# ece411_t2_schematic_5.net
KiCad netlist of a schematic drawn in EAGLE
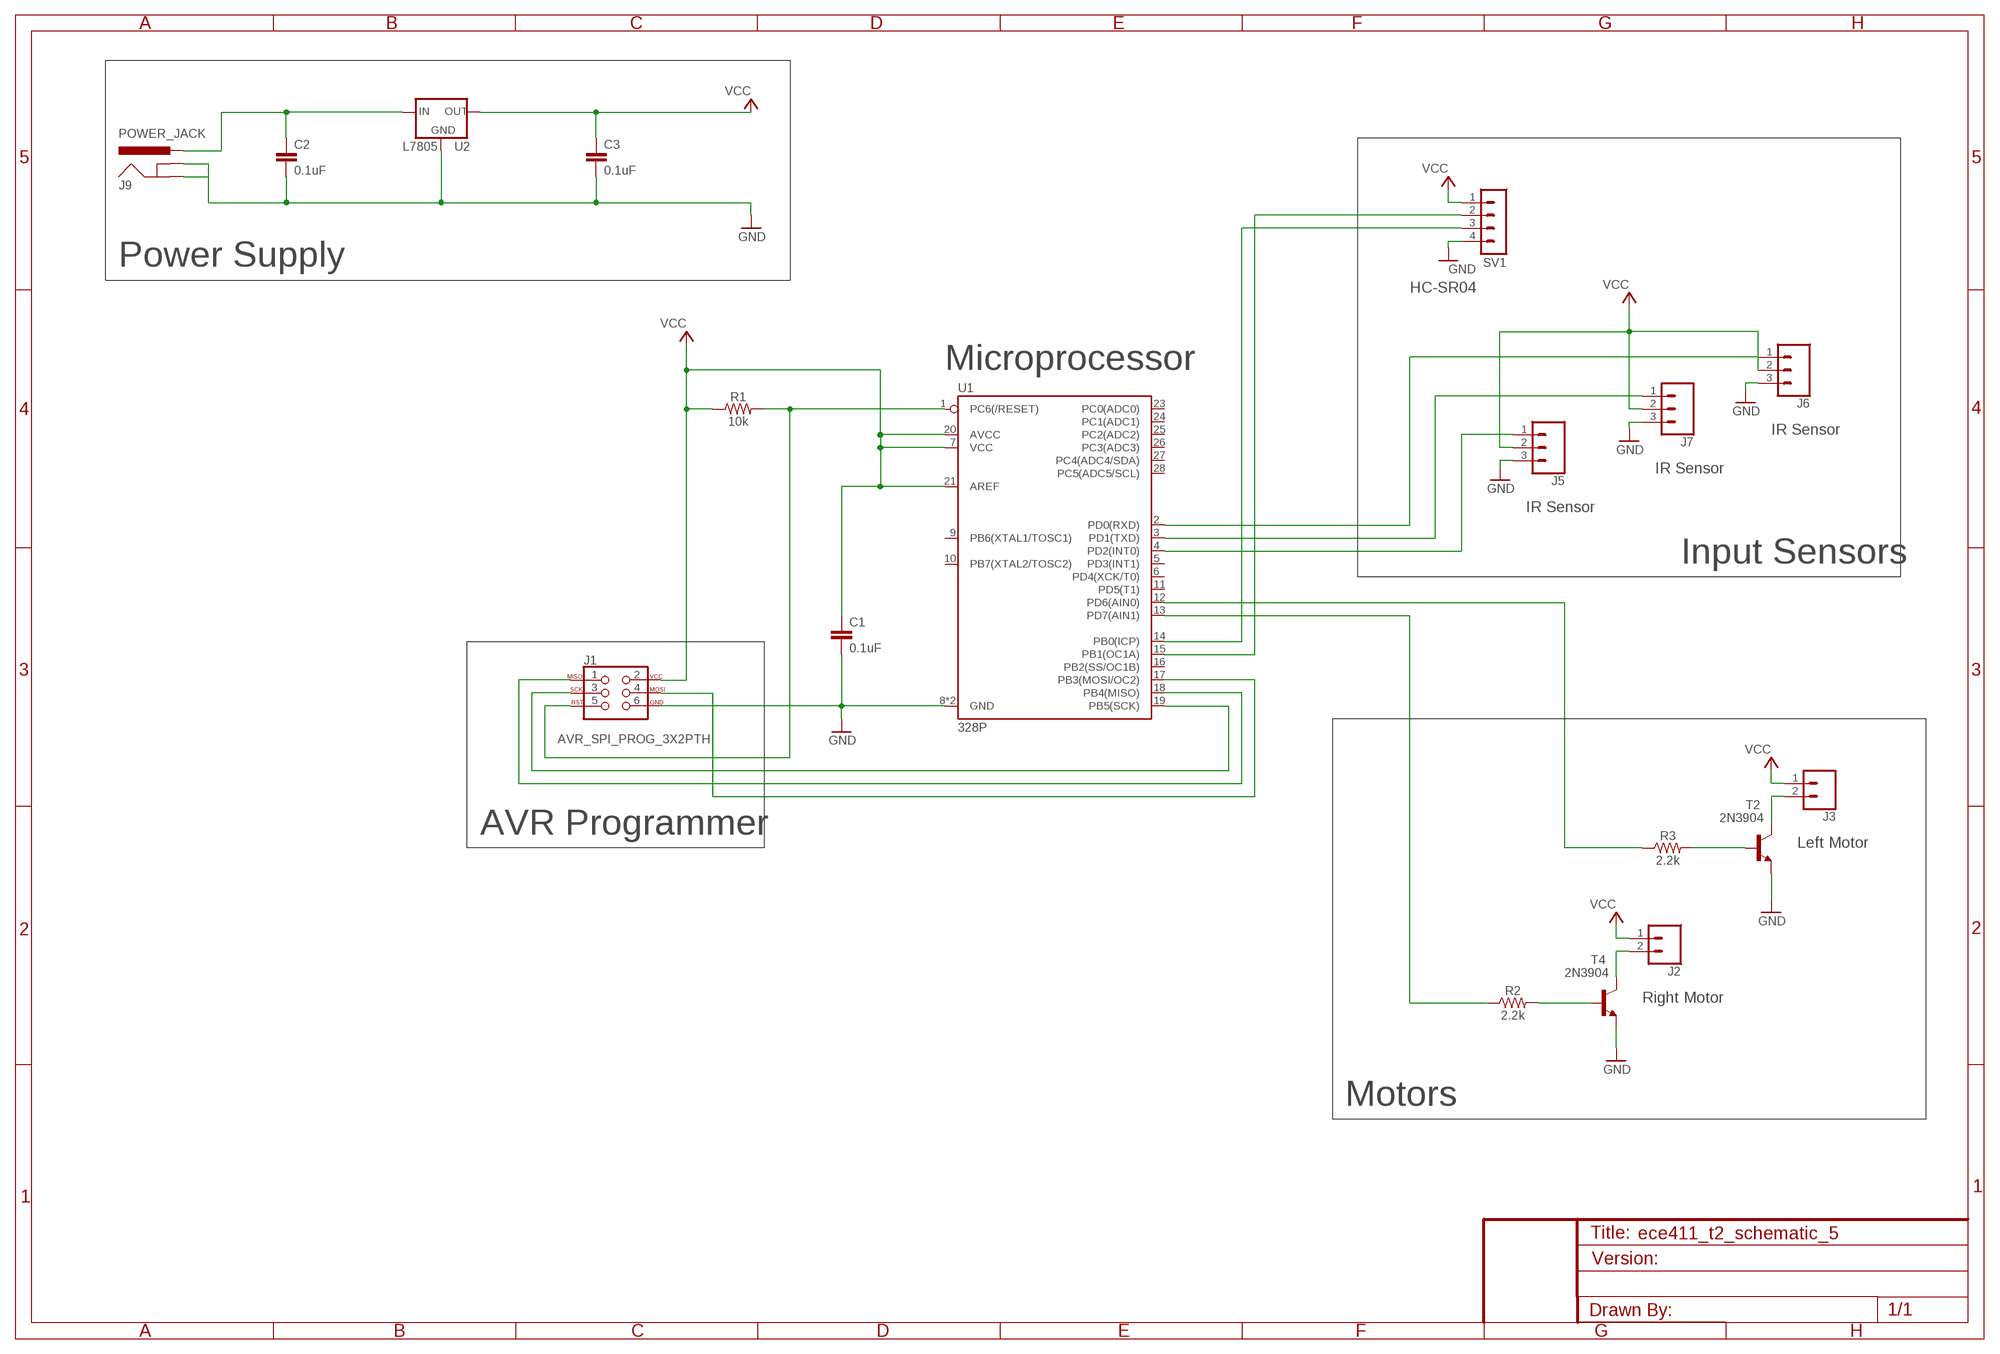
[diagram p0: schematic, sheet 1]

(export (version "E")
  (design (tool "Eeschema 10.0.6"))
  (components
    (comp (ref "C1")
      (value "0.1uF")
      (footprint "eagle-import:0402")
      (libsource (lib "eagle-import") (part "0.1UF-0402-6.3V-10%-X7R"))
    )
    (comp (ref "C2")
      (value "0.1uF")
      (footprint "eagle-import:0402")
      (libsource (lib "eagle-import") (part "0.1UF-0402-6.3V-10%-X7R"))
    )
    (comp (ref "C3")
      (value "0.1uF")
      (footprint "eagle-import:0402")
      (libsource (lib "eagle-import") (part "0.1UF-0402-6.3V-10%-X7R"))
    )
    (comp (ref "J1")
      (value "AVR_SPI_PROG_3X2PTH")
      (footprint "eagle-import:2X3")
      (libsource (lib "eagle-import") (part "AVR_SPI_PROG_3X2PTH"))
    )
    (comp (ref "J2")
      (value "CONN_02")
      (footprint "eagle-import:1X02")
      (libsource (lib "eagle-import") (part "CONN_02"))
    )
    (comp (ref "J3")
      (value "CONN_02")
      (footprint "eagle-import:1X02")
      (libsource (lib "eagle-import") (part "CONN_02"))
    )
    (comp (ref "J5")
      (value "455-1750-1-ND")
      (footprint "eagle-import:1X03")
      (libsource (lib "eagle-import") (part "CONN_03"))
    )
    (comp (ref "J6")
      (value "455-1750-1-ND")
      (footprint "eagle-import:1X03")
      (libsource (lib "eagle-import") (part "CONN_03"))
    )
    (comp (ref "J7")
      (value "455-1750-1-ND")
      (footprint "eagle-import:1X03")
      (libsource (lib "eagle-import") (part "CONN_03"))
    )
    (comp (ref "J9")
      (value "POWER_JACK")
      (footprint "eagle-import:POWER_JACK_PTH")
      (libsource (lib "eagle-import") (part "POWER_JACK"))
    )
    (comp (ref "R1")
      (value "10k")
      (footprint "eagle-import:0402")
      (libsource (lib "eagle-import") (part "10KOHM-0402-1/16W-1%"))
    )
    (comp (ref "R2")
      (value "2.2k")
      (footprint "eagle-import:0603")
      (libsource (lib "eagle-import") (part "2.2KOHM-0603-1/10W-1%"))
    )
    (comp (ref "R3")
      (value "2.2k")
      (footprint "eagle-import:0603")
      (libsource (lib "eagle-import") (part "2.2KOHM-0603-1/10W-1%"))
    )
    (comp (ref "SV1")
      (value "MA04-1")
      (footprint "eagle-import:MA04-1")
      (libsource (lib "eagle-import") (part "MA04-1"))
    )
    (comp (ref "T2")
      (value "2N3904")
      (footprint "eagle-import:TO92")
      (libsource (lib "eagle-import") (part "2N3904"))
    )
    (comp (ref "T4")
      (value "2N3904")
      (footprint "eagle-import:TO92")
      (libsource (lib "eagle-import") (part "2N3904"))
    )
    (comp (ref "U1")
      (value "328P")
      (footprint "eagle-import:DIP28")
      (libsource (lib "eagle-import") (part "ATMEGA328P_PDIP"))
    )
    (comp (ref "U2")
      (value "V_REG_78XX-TO-220")
      (footprint "eagle-import:TO-220-ALT")
      (libsource (lib "eagle-import") (part "V_REG_78XX-TO-220"))
    )
  )
  (nets
    (net (code "1") (name "GND") (class "Default")
      (node (ref "C1") (pin "2") (pinfunction "2_2") (pintype "passive"))
      (node (ref "C2") (pin "2") (pinfunction "2_2") (pintype "passive"))
      (node (ref "C3") (pin "2") (pinfunction "2_2") (pintype "passive"))
      (node (ref "J1") (pin "6") (pinfunction "6_6") (pintype "passive"))
      (node (ref "J5") (pin "3") (pinfunction "3_3") (pintype "passive"))
      (node (ref "J6") (pin "3") (pinfunction "3_3") (pintype "passive"))
      (node (ref "J7") (pin "3") (pinfunction "3_3") (pintype "passive"))
      (node (ref "J9") (pin "GNDBREAK") (pinfunction "GNDBREAK_GNDBREAK") (pintype "bidirectional"))
      (node (ref "SV1") (pin "4") (pinfunction "4_4") (pintype "passive"))
      (node (ref "T2") (pin "3") (pinfunction "E_3") (pintype "passive"))
      (node (ref "T4") (pin "3") (pinfunction "E_3") (pintype "passive"))
      (node (ref "U1") (pin "22") (pinfunction "GND_22") (pintype "bidirectional"))
      (node (ref "U1") (pin "8") (pinfunction "GND_8") (pintype "bidirectional"))
      (node (ref "U2") (pin "GND") (pinfunction "GND_GND") (pintype "input"))
    )
    (net (code "2") (name "Net-(C2-Pad1)") (class "Default")
      (node (ref "C2") (pin "1") (pinfunction "1_1") (pintype "passive"))
      (node (ref "J9") (pin "PWR") (pinfunction "PWR_PWR") (pintype "bidirectional"))
      (node (ref "U2") (pin "IN") (pinfunction "IN_IN") (pintype "input"))
    )
    (net (code "3") (name "Net-(T2-B)") (class "Default")
      (node (ref "R3") (pin "2") (pinfunction "2_2") (pintype "passive"))
      (node (ref "T2") (pin "2") (pinfunction "B_2") (pintype "passive"))
    )
    (net (code "4") (name "Net-(T2-C)") (class "Default")
      (node (ref "J3") (pin "2") (pinfunction "2_2") (pintype "passive"))
      (node (ref "T2") (pin "1") (pinfunction "C_1") (pintype "passive"))
    )
    (net (code "5") (name "Net-(T4-B)") (class "Default")
      (node (ref "R2") (pin "2") (pinfunction "2_2") (pintype "passive"))
      (node (ref "T4") (pin "2") (pinfunction "B_2") (pintype "passive"))
    )
    (net (code "6") (name "Net-(U1-PB0(ICP))") (class "Default")
      (node (ref "SV1") (pin "3") (pinfunction "3_3") (pintype "passive"))
      (node (ref "U1") (pin "14") (pinfunction "PB0(ICP)_14") (pintype "bidirectional"))
    )
    (net (code "7") (name "Net-(U1-PB1(OC1A))") (class "Default")
      (node (ref "SV1") (pin "2") (pinfunction "2_2") (pintype "passive"))
      (node (ref "U1") (pin "15") (pinfunction "PB1(OC1A)_15") (pintype "bidirectional"))
    )
    (net (code "8") (name "Net-(U1-PB3(MOSI{slash}OC2))") (class "Default")
      (node (ref "J1") (pin "4") (pinfunction "4_4") (pintype "passive"))
      (node (ref "U1") (pin "17") (pinfunction "PB3(MOSI/OC2)_17") (pintype "bidirectional"))
    )
    (net (code "9") (name "Net-(U1-PB4(MISO))") (class "Default")
      (node (ref "J1") (pin "1") (pinfunction "1_1") (pintype "passive"))
      (node (ref "U1") (pin "18") (pinfunction "PB4(MISO)_18") (pintype "bidirectional"))
    )
    (net (code "10") (name "Net-(U1-PB5(SCK))") (class "Default")
      (node (ref "J1") (pin "3") (pinfunction "3_3") (pintype "passive"))
      (node (ref "U1") (pin "19") (pinfunction "PB5(SCK)_19") (pintype "bidirectional"))
    )
    (net (code "11") (name "Net-(U1-PC6({slash}RESET))") (class "Default")
      (node (ref "J1") (pin "5") (pinfunction "5_5") (pintype "passive"))
      (node (ref "R1") (pin "2") (pinfunction "2_2") (pintype "passive"))
      (node (ref "U1") (pin "1") (pinfunction "PC6(/RESET)_1") (pintype "bidirectional"))
    )
    (net (code "12") (name "Net-(U1-PD0(RXD))") (class "Default")
      (node (ref "J6") (pin "1") (pinfunction "1_1") (pintype "passive"))
      (node (ref "U1") (pin "2") (pinfunction "PD0(RXD)_2") (pintype "bidirectional"))
    )
    (net (code "13") (name "Net-(U1-PD1(TXD))") (class "Default")
      (node (ref "J7") (pin "1") (pinfunction "1_1") (pintype "passive"))
      (node (ref "U1") (pin "3") (pinfunction "PD1(TXD)_3") (pintype "bidirectional"))
    )
    (net (code "14") (name "Net-(U1-PD2(INT0))") (class "Default")
      (node (ref "J5") (pin "1") (pinfunction "1_1") (pintype "passive"))
      (node (ref "U1") (pin "4") (pinfunction "PD2(INT0)_4") (pintype "bidirectional"))
    )
    (net (code "15") (name "Net-(U1-PD6(AIN0))") (class "Default")
      (node (ref "R3") (pin "1") (pinfunction "1_1") (pintype "passive"))
      (node (ref "U1") (pin "12") (pinfunction "PD6(AIN0)_12") (pintype "bidirectional"))
    )
    (net (code "16") (name "Net-(U1-PD7(AIN1))") (class "Default")
      (node (ref "R2") (pin "1") (pinfunction "1_1") (pintype "passive"))
      (node (ref "U1") (pin "13") (pinfunction "PD7(AIN1)_13") (pintype "bidirectional"))
    )
    (net (code "17") (name "VCC") (class "Default")
      (node (ref "C1") (pin "1") (pinfunction "1_1") (pintype "passive"))
      (node (ref "C3") (pin "1") (pinfunction "1_1") (pintype "passive"))
      (node (ref "J1") (pin "2") (pinfunction "2_2") (pintype "passive"))
      (node (ref "J2") (pin "1") (pinfunction "1_1") (pintype "passive"))
      (node (ref "J2") (pin "2") (pinfunction "2_2") (pintype "passive"))
      (node (ref "J3") (pin "1") (pinfunction "1_1") (pintype "passive"))
      (node (ref "J5") (pin "2") (pinfunction "2_2") (pintype "passive"))
      (node (ref "J6") (pin "2") (pinfunction "2_2") (pintype "passive"))
      (node (ref "J7") (pin "2") (pinfunction "2_2") (pintype "passive"))
      (node (ref "R1") (pin "1") (pinfunction "1_1") (pintype "passive"))
      (node (ref "SV1") (pin "1") (pinfunction "1_1") (pintype "passive"))
      (node (ref "T4") (pin "1") (pinfunction "C_1") (pintype "passive"))
      (node (ref "U1") (pin "20") (pinfunction "AVCC_20") (pintype "bidirectional"))
      (node (ref "U1") (pin "21") (pinfunction "AREF_21") (pintype "bidirectional"))
      (node (ref "U1") (pin "7") (pinfunction "VCC_7") (pintype "bidirectional"))
      (node (ref "U2") (pin "OUT") (pinfunction "OUT_OUT") (pintype "passive"))
    )
    (net (code "18") (name "unconnected-(J9-PadGND)") (class "Default")
      (node (ref "J9") (pin "GND") (pinfunction "GND_GND") (pintype "bidirectional"))
    )
    (net (code "19") (name "unconnected-(U1-PB2(SS{slash}OC1B)-Pad16)") (class "Default")
      (node (ref "U1") (pin "16") (pinfunction "PB2(SS/OC1B)_16") (pintype "bidirectional"))
    )
    (net (code "20") (name "unconnected-(U1-PB6(XTAL1{slash}TOSC1)-Pad9)") (class "Default")
      (node (ref "U1") (pin "9") (pinfunction "PB6(XTAL1/TOSC1)_9") (pintype "bidirectional"))
    )
    (net (code "21") (name "unconnected-(U1-PB7(XTAL2{slash}TOSC2)-Pad10)") (class "Default")
      (node (ref "U1") (pin "10") (pinfunction "PB7(XTAL2/TOSC2)_10") (pintype "bidirectional"))
    )
    (net (code "22") (name "unconnected-(U1-PC0(ADC0)-Pad23)") (class "Default")
      (node (ref "U1") (pin "23") (pinfunction "PC0(ADC0)_23") (pintype "bidirectional"))
    )
    (net (code "23") (name "unconnected-(U1-PC1(ADC1)-Pad24)") (class "Default")
      (node (ref "U1") (pin "24") (pinfunction "PC1(ADC1)_24") (pintype "bidirectional"))
    )
    (net (code "24") (name "unconnected-(U1-PC2(ADC2)-Pad25)") (class "Default")
      (node (ref "U1") (pin "25") (pinfunction "PC2(ADC2)_25") (pintype "bidirectional"))
    )
    (net (code "25") (name "unconnected-(U1-PC3(ADC3)-Pad26)") (class "Default")
      (node (ref "U1") (pin "26") (pinfunction "PC3(ADC3)_26") (pintype "bidirectional"))
    )
    (net (code "26") (name "unconnected-(U1-PC4(ADC4{slash}SDA)-Pad27)") (class "Default")
      (node (ref "U1") (pin "27") (pinfunction "PC4(ADC4/SDA)_27") (pintype "bidirectional"))
    )
    (net (code "27") (name "unconnected-(U1-PC5(ADC5{slash}SCL)-Pad28)") (class "Default")
      (node (ref "U1") (pin "28") (pinfunction "PC5(ADC5/SCL)_28") (pintype "bidirectional"))
    )
    (net (code "28") (name "unconnected-(U1-PD3(INT1)-Pad5)") (class "Default")
      (node (ref "U1") (pin "5") (pinfunction "PD3(INT1)_5") (pintype "bidirectional"))
    )
    (net (code "29") (name "unconnected-(U1-PD4(XCK{slash}T0)-Pad6)") (class "Default")
      (node (ref "U1") (pin "6") (pinfunction "PD4(XCK/T0)_6") (pintype "bidirectional"))
    )
    (net (code "30") (name "unconnected-(U1-PD5(T1)-Pad11)") (class "Default")
      (node (ref "U1") (pin "11") (pinfunction "PD5(T1)_11") (pintype "bidirectional"))
    )
  )
)
